# Time4CM4_SIT_module.net
KiCad netlist of a schematic drawn in Altium Designer
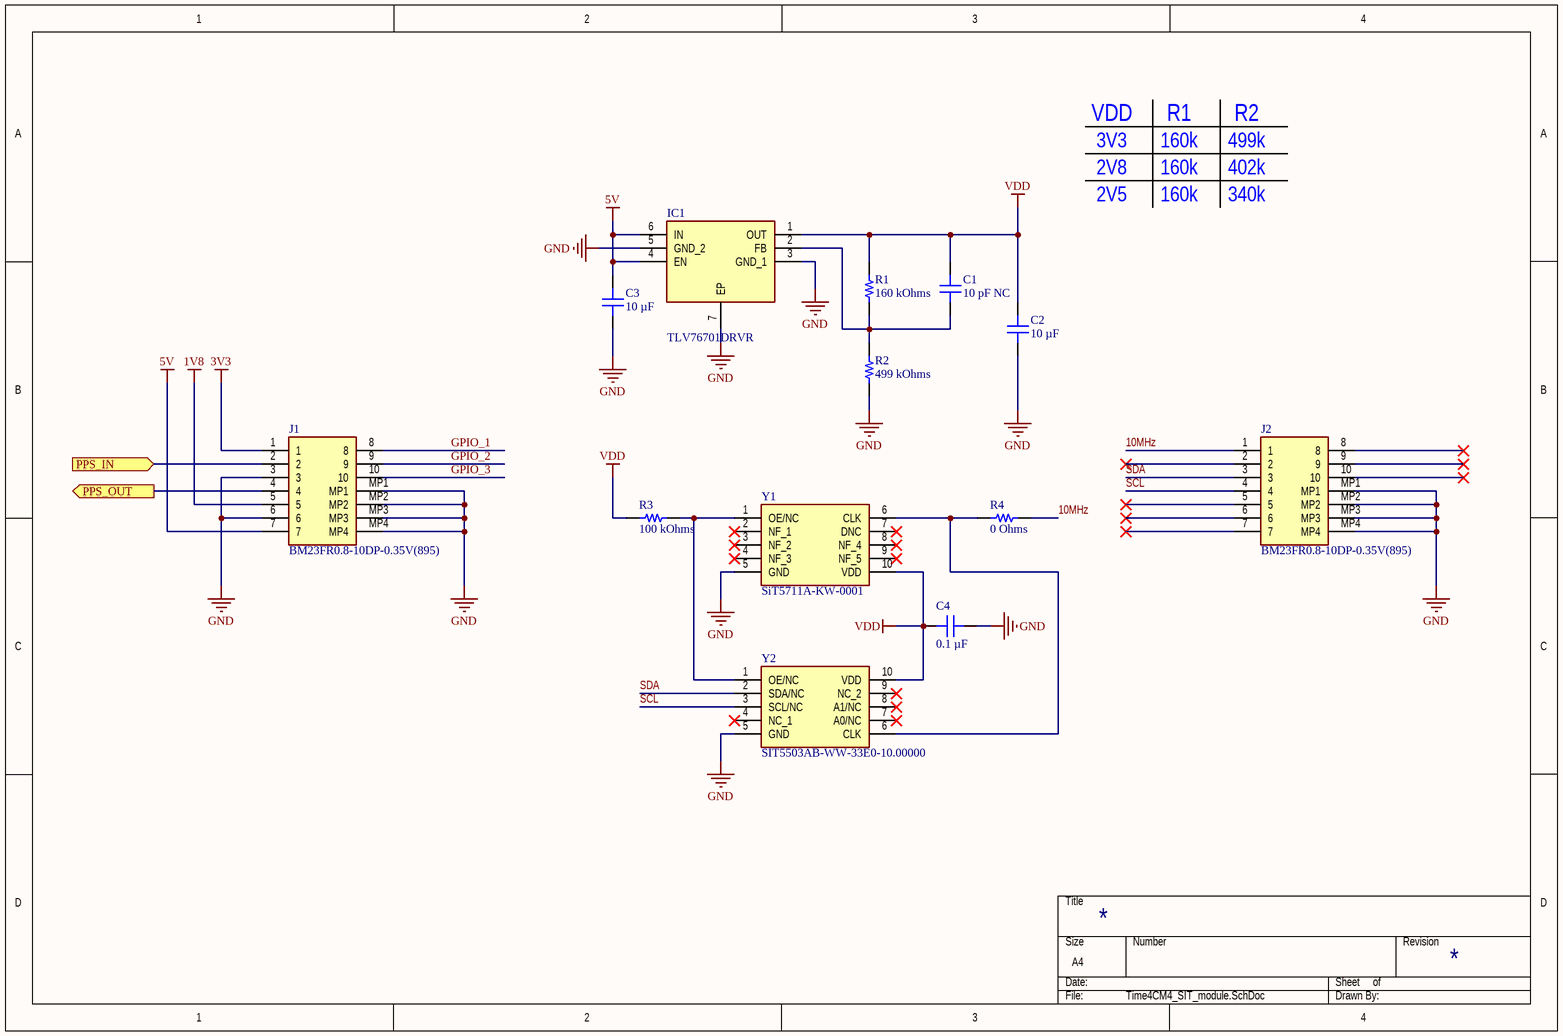
[diagram p0: Time4CM4_SIT_module.SchDoc]

(export (version "E")
  (design (tool "Eeschema 10.0.6"))
  (components
    (comp (ref "C1")
      (value "10 pF NC")
      (footprint "CAP 0402_1005")
      (description "CAP CER 10PF 50V C0G/NPO 0402")
      (fields (field (name "PART NUMBER") "CC0402KRNPO9BN100") (field (name "MANUFACTURER") "Yageo"))
      (libsource (lib "Celestial Altium Library - altium_library") (part "Capacitor"))
    )
    (comp (ref "C2")
      (value "10 µF")
      (footprint "CAP 0603_1608")
      (description "CAP CER 10UF 6.3V X5R 0603")
      (fields (field (name "PART NUMBER") "CC0603MPX5R5BB106") (field (name "MANUFACTURER") "Yageo"))
      (libsource (lib "Celestial Altium Library - altium_library") (part "Capacitor"))
    )
    (comp (ref "C3")
      (value "10 µF")
      (footprint "CAP 0603_1608")
      (description "CAP CER 10UF 6.3V X5R 0603")
      (fields (field (name "PART NUMBER") "CC0603MPX5R5BB106") (field (name "MANUFACTURER") "Yageo"))
      (libsource (lib "Celestial Altium Library - altium_library") (part "Capacitor"))
    )
    (comp (ref "C4")
      (value "0.1 µF")
      (footprint "CAP 0402_1005")
      (description "CAP CER 0.1UF 6.3V X7R 0402")
      (fields (field (name "PART NUMBER") "CC0402KRX7R5BB104") (field (name "MANUFACTURER") "Yageo"))
      (libsource (lib "Celestial Altium Library - altium_library") (part "Capacitor"))
    )
    (comp (ref "IC1")
      (value "TLV76701DRVR")
      (footprint "SamacSys:SON65P200X200X80-7N")
      (description "IC REG LINEAR POS ADJ 1A 6WSON")
      (fields (field (name "MOUSER PART NUMBER") "595-TLV76701DRVR"))
      (libsource (lib "SamacSys") (part "TLV76701DRVR"))
    )
    (comp (ref "J1")
      (value "BM23FR0.8-10DP-0.35V(895)")
      (footprint "SamacSys:BM23FR0810DP035V895")
      (description "Connector")
      (fields
        (field (name "MANUFACTURER_PART_NUMBER") "BM23FR0.8-10DS-0.35V(895)")
        (field (name "MOUSER PART NUMBER") "798-3FR0810DS035V895")
      )
      (libsource (lib "*") (part "BM23FR0.8-10DS-0.35V_895_"))
    )
    (comp (ref "J2")
      (value "BM23FR0.8-10DP-0.35V(895)")
      (footprint "SamacSys:BM23FR0810DP035V895")
      (description "Connector")
      (fields
        (field (name "MANUFACTURER_PART_NUMBER") "BM23FR0.8-10DS-0.35V(895)")
        (field (name "MOUSER PART NUMBER") "798-3FR0810DS035V895")
      )
      (libsource (lib "*") (part "BM23FR0.8-10DS-0.35V_895_"))
    )
    (comp (ref "R1")
      (value "160 kOhms")
      (footprint "YAGEO RES 0402_1005")
      (description "RES 160K OHM 1% 1/16W 0402")
      (fields (field (name "PART NUMBER") "RC0402FR-07160KL") (field (name "MANUFACTURER") "Yageo"))
      (libsource (lib "Celestial Altium Library - altium_library") (part "Resistor"))
    )
    (comp (ref "R2")
      (value "499 kOhms")
      (footprint "YAGEO RES 0402_1005")
      (description "RES 499K OHM 1% 1/16W 0402")
      (fields (field (name "PART NUMBER") "RC0402FR-07499KL") (field (name "MANUFACTURER") "Yageo"))
      (libsource (lib "Celestial Altium Library - altium_library") (part "Resistor"))
    )
    (comp (ref "R3")
      (value "100 kOhms")
      (footprint "YAGEO RES 0402_1005")
      (description "RES 100K OHM 1% 1/16W 0402")
      (fields (field (name "PART NUMBER") "RC0402FR-07100KL") (field (name "MANUFACTURER") "Yageo"))
      (libsource (lib "Celestial Altium Library - altium_library") (part "Resistor"))
    )
    (comp (ref "R4")
      (value "0 Ohms")
      (footprint "YAGEO RES 0402_1005")
      (description "RES 0 OHM JUMPER 1/16W 0402")
      (fields (field (name "PART NUMBER") "RC0402FR-070RL") (field (name "MANUFACTURER") "Yageo"))
      (libsource (lib "Celestial Altium Library - altium_library") (part "Resistor"))
    )
    (comp (ref "Y1")
      (value "SiT5711A-KW-0001")
      (footprint "SamacSys:Emerald_9070_10pins_2022")
      (description "Crystal or Oscillator")
      (libsource (lib "SamacSys") (part "SiT5711A-KW-0001"))
    )
    (comp (ref "Y2")
      (value "SIT5503AB-WW-33E0-10.00000")
      (footprint "SamacSys:Ceramic_QFN_7050_10pins")
      (description "Crystal or Oscillator")
      (libsource (lib "SamacSys") (part "SIT5503AB-WW-33E0-10.00000"))
    )
  )
  (nets
    (net (code "1") (name "/10MHz") (class "Default")
      (node (ref "J2") (pin "1") (pinfunction "1_1") (pintype "passive"))
      (node (ref "R4") (pin "1") (pinfunction "1_1") (pintype "passive"))
    )
    (net (code "2") (name "/GPIO_1") (class "Default")
      (node (ref "J1") (pin "8") (pinfunction "8_8") (pintype "passive"))
    )
    (net (code "3") (name "/GPIO_2") (class "Default")
      (node (ref "J1") (pin "9") (pinfunction "9_9") (pintype "passive"))
    )
    (net (code "4") (name "/GPIO_3") (class "Default")
      (node (ref "J1") (pin "10") (pinfunction "10_10") (pintype "passive"))
    )
    (net (code "5") (name "/PPS_IN") (class "Default")
      (node (ref "J1") (pin "2") (pinfunction "2_2") (pintype "passive"))
    )
    (net (code "6") (name "/PPS_OUT") (class "Default")
      (node (ref "J1") (pin "4") (pinfunction "4_4") (pintype "passive"))
    )
    (net (code "7") (name "/SCL") (class "Default")
      (node (ref "J2") (pin "4") (pinfunction "4_4") (pintype "passive"))
      (node (ref "Y2") (pin "3") (pinfunction "SCL/NC_3") (pintype "passive"))
    )
    (net (code "8") (name "/SDA") (class "Default")
      (node (ref "J2") (pin "3") (pinfunction "3_3") (pintype "passive"))
      (node (ref "Y2") (pin "2") (pinfunction "SDA/NC_2") (pintype "passive"))
    )
    (net (code "9") (name "1V8") (class "Default")
      (node (ref "J1") (pin "5") (pinfunction "5_5") (pintype "passive"))
    )
    (net (code "10") (name "3V3") (class "Default")
      (node (ref "J1") (pin "1") (pinfunction "1_1") (pintype "passive"))
    )
    (net (code "11") (name "5V") (class "Default")
      (node (ref "C3") (pin "2") (pinfunction "2_2") (pintype "passive"))
      (node (ref "IC1") (pin "4") (pinfunction "EN_4") (pintype "passive"))
      (node (ref "IC1") (pin "6") (pinfunction "IN_6") (pintype "passive"))
      (node (ref "J1") (pin "7") (pinfunction "7_7") (pintype "passive"))
    )
    (net (code "12") (name "GND") (class "Default")
      (node (ref "C2") (pin "1") (pinfunction "1_1") (pintype "passive"))
      (node (ref "C3") (pin "1") (pinfunction "1_1") (pintype "passive"))
      (node (ref "C4") (pin "1") (pinfunction "1_1") (pintype "passive"))
      (node (ref "IC1") (pin "3") (pinfunction "GND_1_3") (pintype "passive"))
      (node (ref "IC1") (pin "5") (pinfunction "GND_2_5") (pintype "passive"))
      (node (ref "IC1") (pin "7") (pinfunction "EP_7") (pintype "passive"))
      (node (ref "J1") (pin "3") (pinfunction "3_3") (pintype "passive"))
      (node (ref "J1") (pin "6") (pinfunction "6_6") (pintype "passive"))
      (node (ref "J1") (pin "MP1") (pinfunction "MP1_MP1") (pintype "passive"))
      (node (ref "J1") (pin "MP2") (pinfunction "MP2_MP2") (pintype "passive"))
      (node (ref "J1") (pin "MP3") (pinfunction "MP3_MP3") (pintype "passive"))
      (node (ref "J1") (pin "MP4") (pinfunction "MP4_MP4") (pintype "passive"))
      (node (ref "J2") (pin "MP1") (pinfunction "MP1_MP1") (pintype "passive"))
      (node (ref "J2") (pin "MP2") (pinfunction "MP2_MP2") (pintype "passive"))
      (node (ref "J2") (pin "MP3") (pinfunction "MP3_MP3") (pintype "passive"))
      (node (ref "J2") (pin "MP4") (pinfunction "MP4_MP4") (pintype "passive"))
      (node (ref "R2") (pin "1") (pinfunction "1_1") (pintype "passive"))
      (node (ref "Y1") (pin "5") (pinfunction "GND_5") (pintype "passive"))
      (node (ref "Y2") (pin "5") (pinfunction "GND_5") (pintype "passive"))
    )
    (net (code "13") (name "Net-(IC1-FB)") (class "Default")
      (node (ref "C1") (pin "1") (pinfunction "1_1") (pintype "passive"))
      (node (ref "IC1") (pin "2") (pinfunction "FB_2") (pintype "passive"))
      (node (ref "R1") (pin "1") (pinfunction "1_1") (pintype "passive"))
      (node (ref "R2") (pin "2") (pinfunction "2_2") (pintype "passive"))
    )
    (net (code "14") (name "Net-(Y1-CLK)") (class "Default")
      (node (ref "R4") (pin "2") (pinfunction "2_2") (pintype "passive"))
      (node (ref "Y1") (pin "6") (pinfunction "CLK_6") (pintype "passive"))
      (node (ref "Y2") (pin "6") (pinfunction "CLK_6") (pintype "passive"))
    )
    (net (code "15") (name "Net-(Y1-OE{slash}NC)") (class "Default")
      (node (ref "R3") (pin "2") (pinfunction "2_2") (pintype "passive"))
      (node (ref "Y1") (pin "1") (pinfunction "OE/NC_1") (pintype "passive"))
      (node (ref "Y2") (pin "1") (pinfunction "OE/NC_1") (pintype "passive"))
    )
    (net (code "16") (name "VDD") (class "Default")
      (node (ref "C1") (pin "2") (pinfunction "2_2") (pintype "passive"))
      (node (ref "C2") (pin "2") (pinfunction "2_2") (pintype "passive"))
      (node (ref "C4") (pin "2") (pinfunction "2_2") (pintype "passive"))
      (node (ref "IC1") (pin "1") (pinfunction "OUT_1") (pintype "passive"))
      (node (ref "R1") (pin "2") (pinfunction "2_2") (pintype "passive"))
      (node (ref "R3") (pin "1") (pinfunction "1_1") (pintype "passive"))
      (node (ref "Y1") (pin "10") (pinfunction "VDD_10") (pintype "passive"))
      (node (ref "Y2") (pin "10") (pinfunction "VDD_10") (pintype "passive"))
    )
    (net (code "17") (name "unconnected-(J2-Pad2)") (class "Default")
      (node (ref "J2") (pin "2") (pinfunction "2_2") (pintype "passive+no_connect"))
    )
    (net (code "18") (name "unconnected-(J2-Pad5)") (class "Default")
      (node (ref "J2") (pin "5") (pinfunction "5_5") (pintype "passive+no_connect"))
    )
    (net (code "19") (name "unconnected-(J2-Pad6)") (class "Default")
      (node (ref "J2") (pin "6") (pinfunction "6_6") (pintype "passive+no_connect"))
    )
    (net (code "20") (name "unconnected-(J2-Pad7)") (class "Default")
      (node (ref "J2") (pin "7") (pinfunction "7_7") (pintype "passive+no_connect"))
    )
    (net (code "21") (name "unconnected-(J2-Pad8)") (class "Default")
      (node (ref "J2") (pin "8") (pinfunction "8_8") (pintype "passive+no_connect"))
    )
    (net (code "22") (name "unconnected-(J2-Pad9)") (class "Default")
      (node (ref "J2") (pin "9") (pinfunction "9_9") (pintype "passive+no_connect"))
    )
    (net (code "23") (name "unconnected-(J2-Pad10)") (class "Default")
      (node (ref "J2") (pin "10") (pinfunction "10_10") (pintype "passive+no_connect"))
    )
    (net (code "24") (name "unconnected-(Y1-DNC-Pad7)") (class "Default")
      (node (ref "Y1") (pin "7") (pinfunction "DNC_7") (pintype "passive+no_connect"))
    )
    (net (code "25") (name "unconnected-(Y1-NF_1-Pad2)") (class "Default")
      (node (ref "Y1") (pin "2") (pinfunction "NF_1_2") (pintype "passive+no_connect"))
    )
    (net (code "26") (name "unconnected-(Y1-NF_2-Pad3)") (class "Default")
      (node (ref "Y1") (pin "3") (pinfunction "NF_2_3") (pintype "passive+no_connect"))
    )
    (net (code "27") (name "unconnected-(Y1-NF_3-Pad4)") (class "Default")
      (node (ref "Y1") (pin "4") (pinfunction "NF_3_4") (pintype "passive+no_connect"))
    )
    (net (code "28") (name "unconnected-(Y1-NF_4-Pad8)") (class "Default")
      (node (ref "Y1") (pin "8") (pinfunction "NF_4_8") (pintype "passive+no_connect"))
    )
    (net (code "29") (name "unconnected-(Y1-NF_5-Pad9)") (class "Default")
      (node (ref "Y1") (pin "9") (pinfunction "NF_5_9") (pintype "passive+no_connect"))
    )
    (net (code "30") (name "unconnected-(Y2-A0{slash}NC-Pad7)") (class "Default")
      (node (ref "Y2") (pin "7") (pinfunction "A0/NC_7") (pintype "passive+no_connect"))
    )
    (net (code "31") (name "unconnected-(Y2-A1{slash}NC-Pad8)") (class "Default")
      (node (ref "Y2") (pin "8") (pinfunction "A1/NC_8") (pintype "passive+no_connect"))
    )
    (net (code "32") (name "unconnected-(Y2-NC_1-Pad4)") (class "Default")
      (node (ref "Y2") (pin "4") (pinfunction "NC_1_4") (pintype "passive+no_connect"))
    )
    (net (code "33") (name "unconnected-(Y2-NC_2-Pad9)") (class "Default")
      (node (ref "Y2") (pin "9") (pinfunction "NC_2_9") (pintype "passive+no_connect"))
    )
  )
)
